# ModulePlayAndCharge.net
KiCad netlist of a schematic drawn in EasyEDA Pro
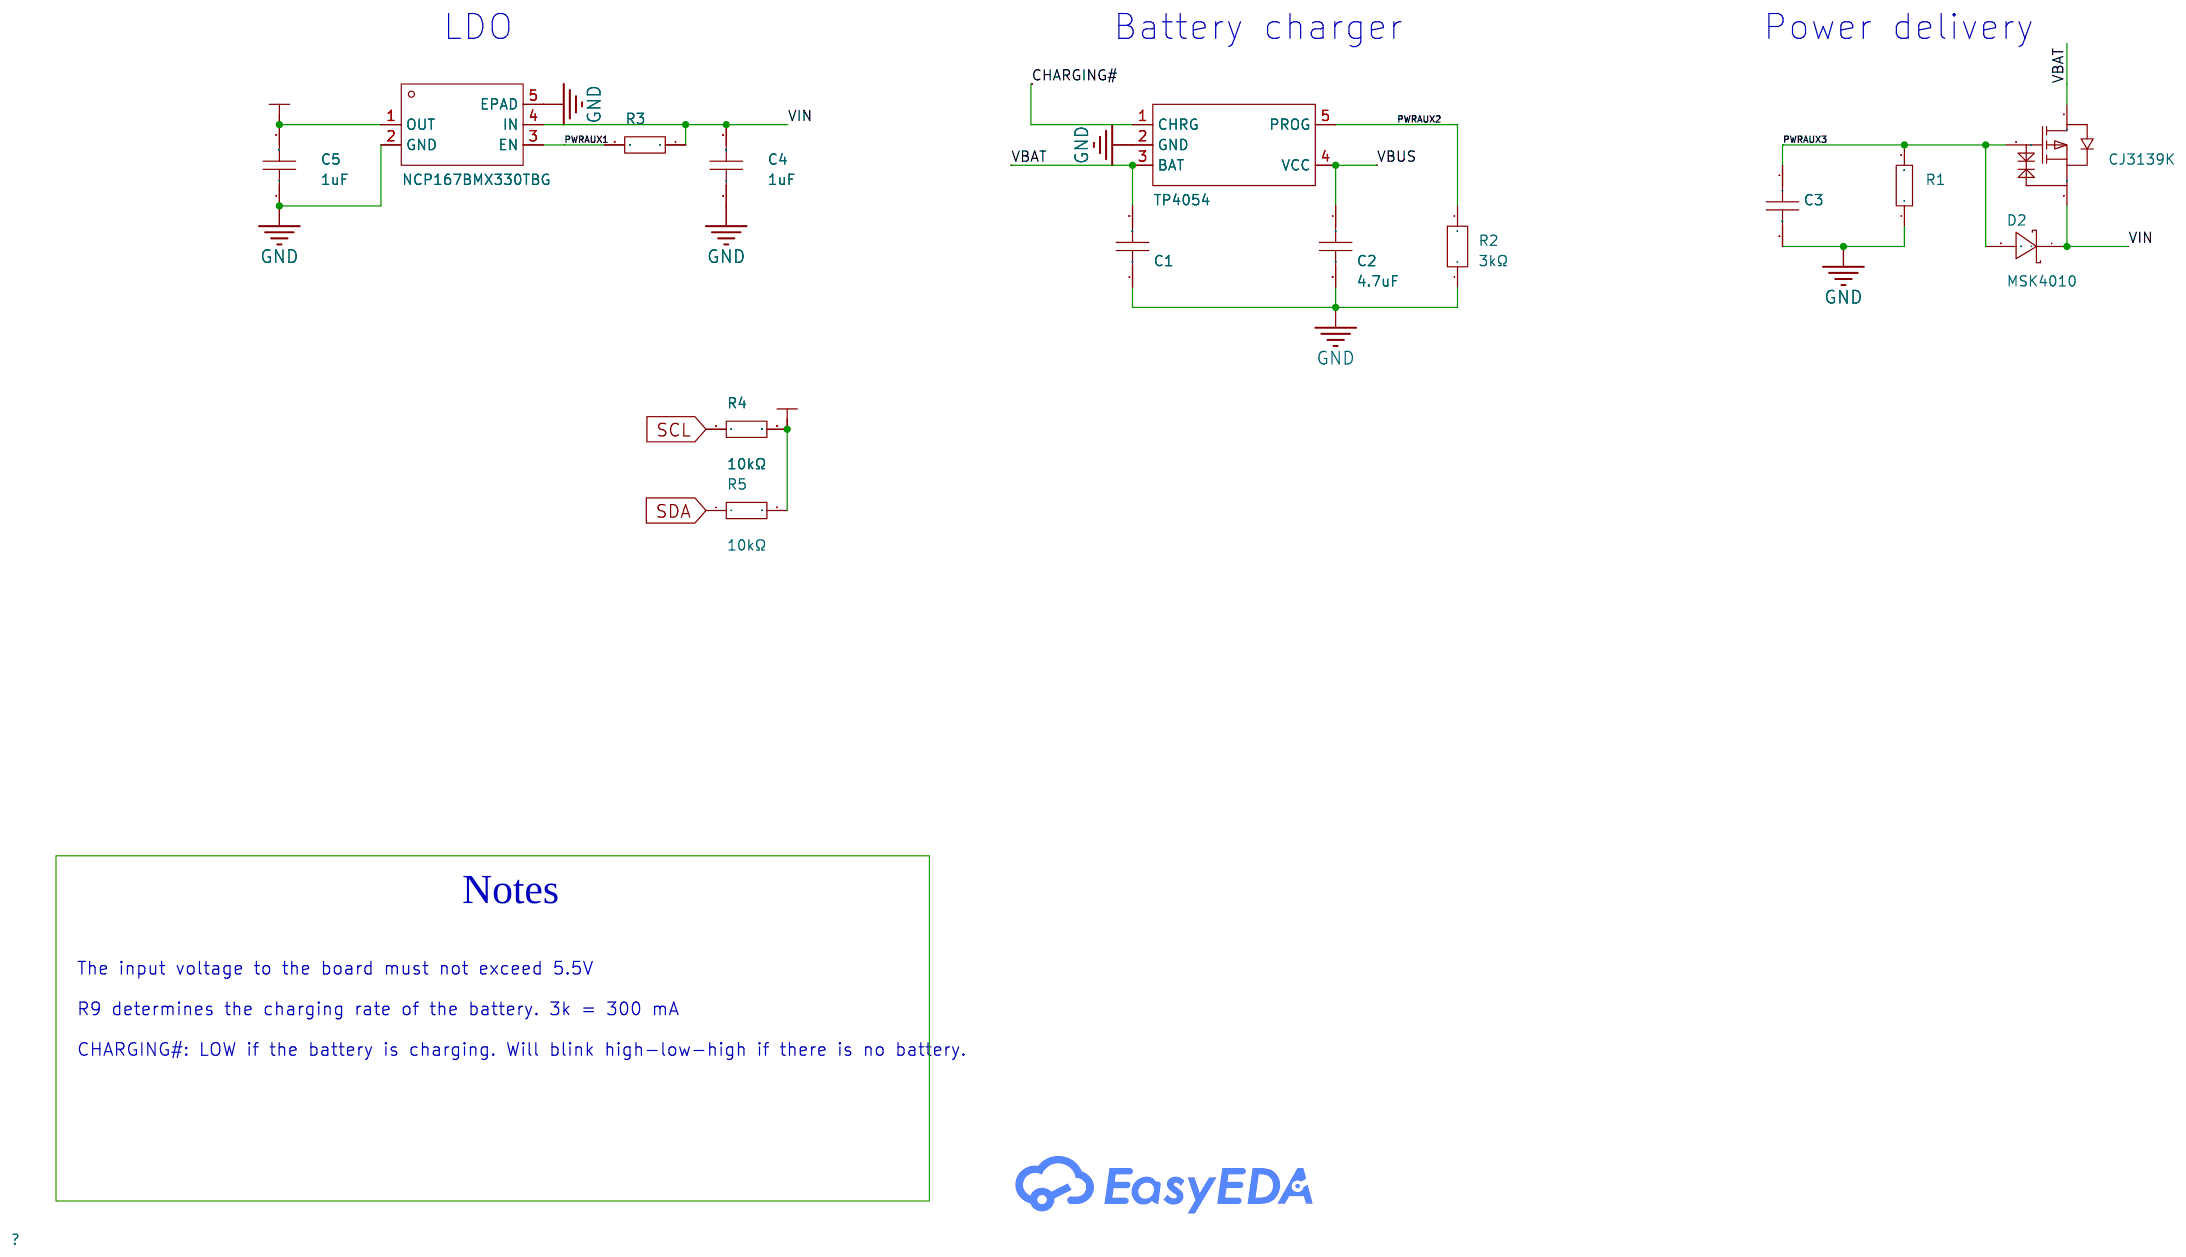
[diagram p0: Power]
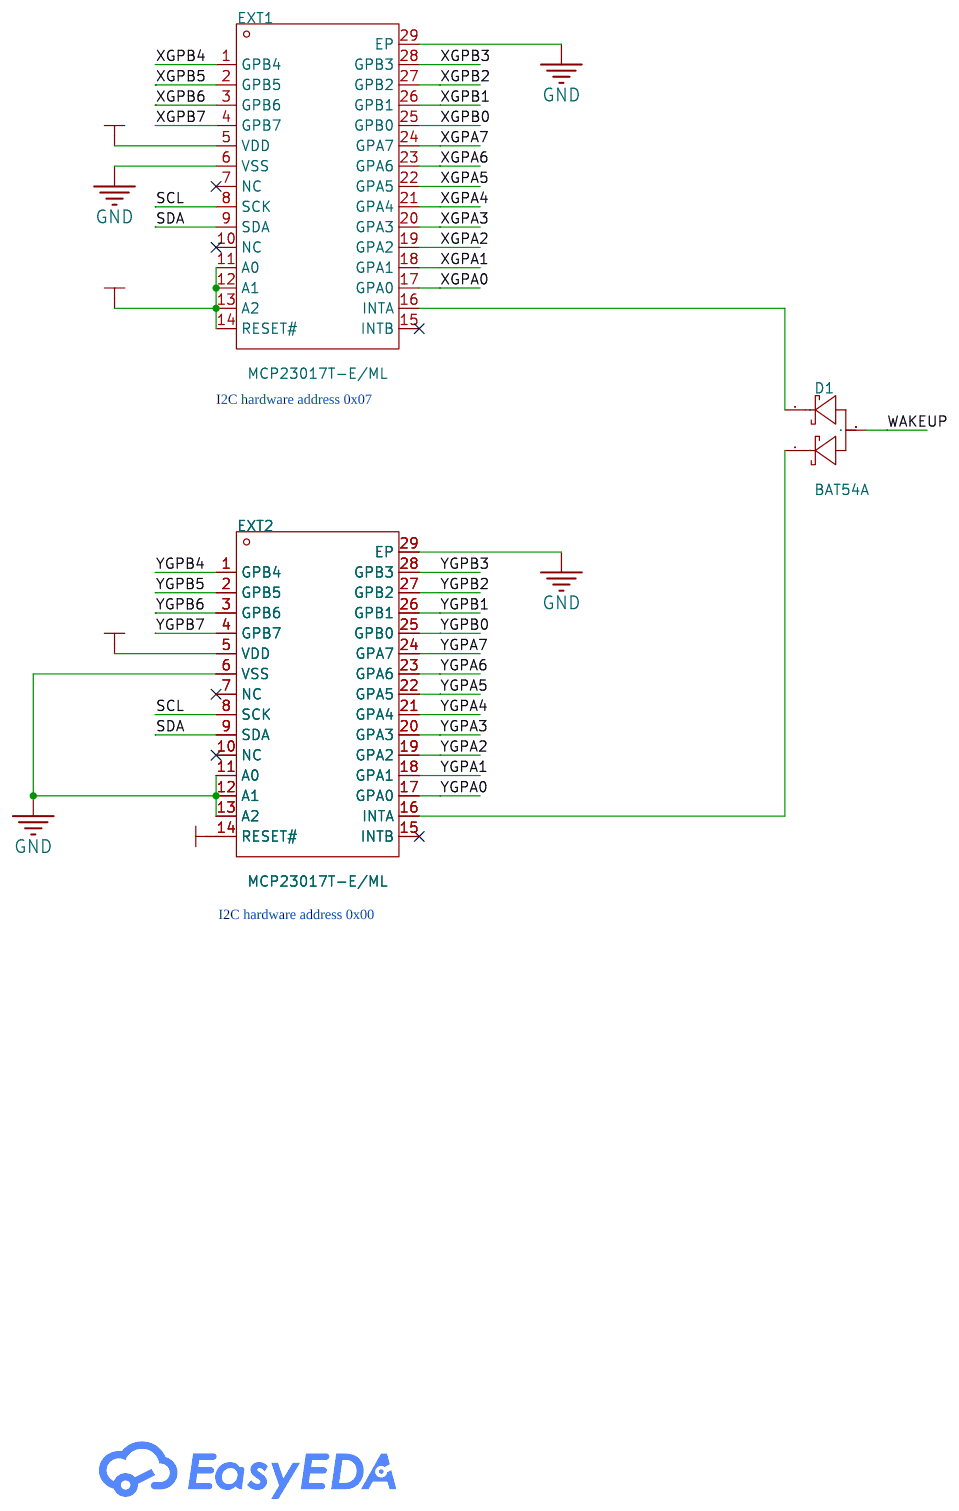
[diagram p1: GPIOExpanders]
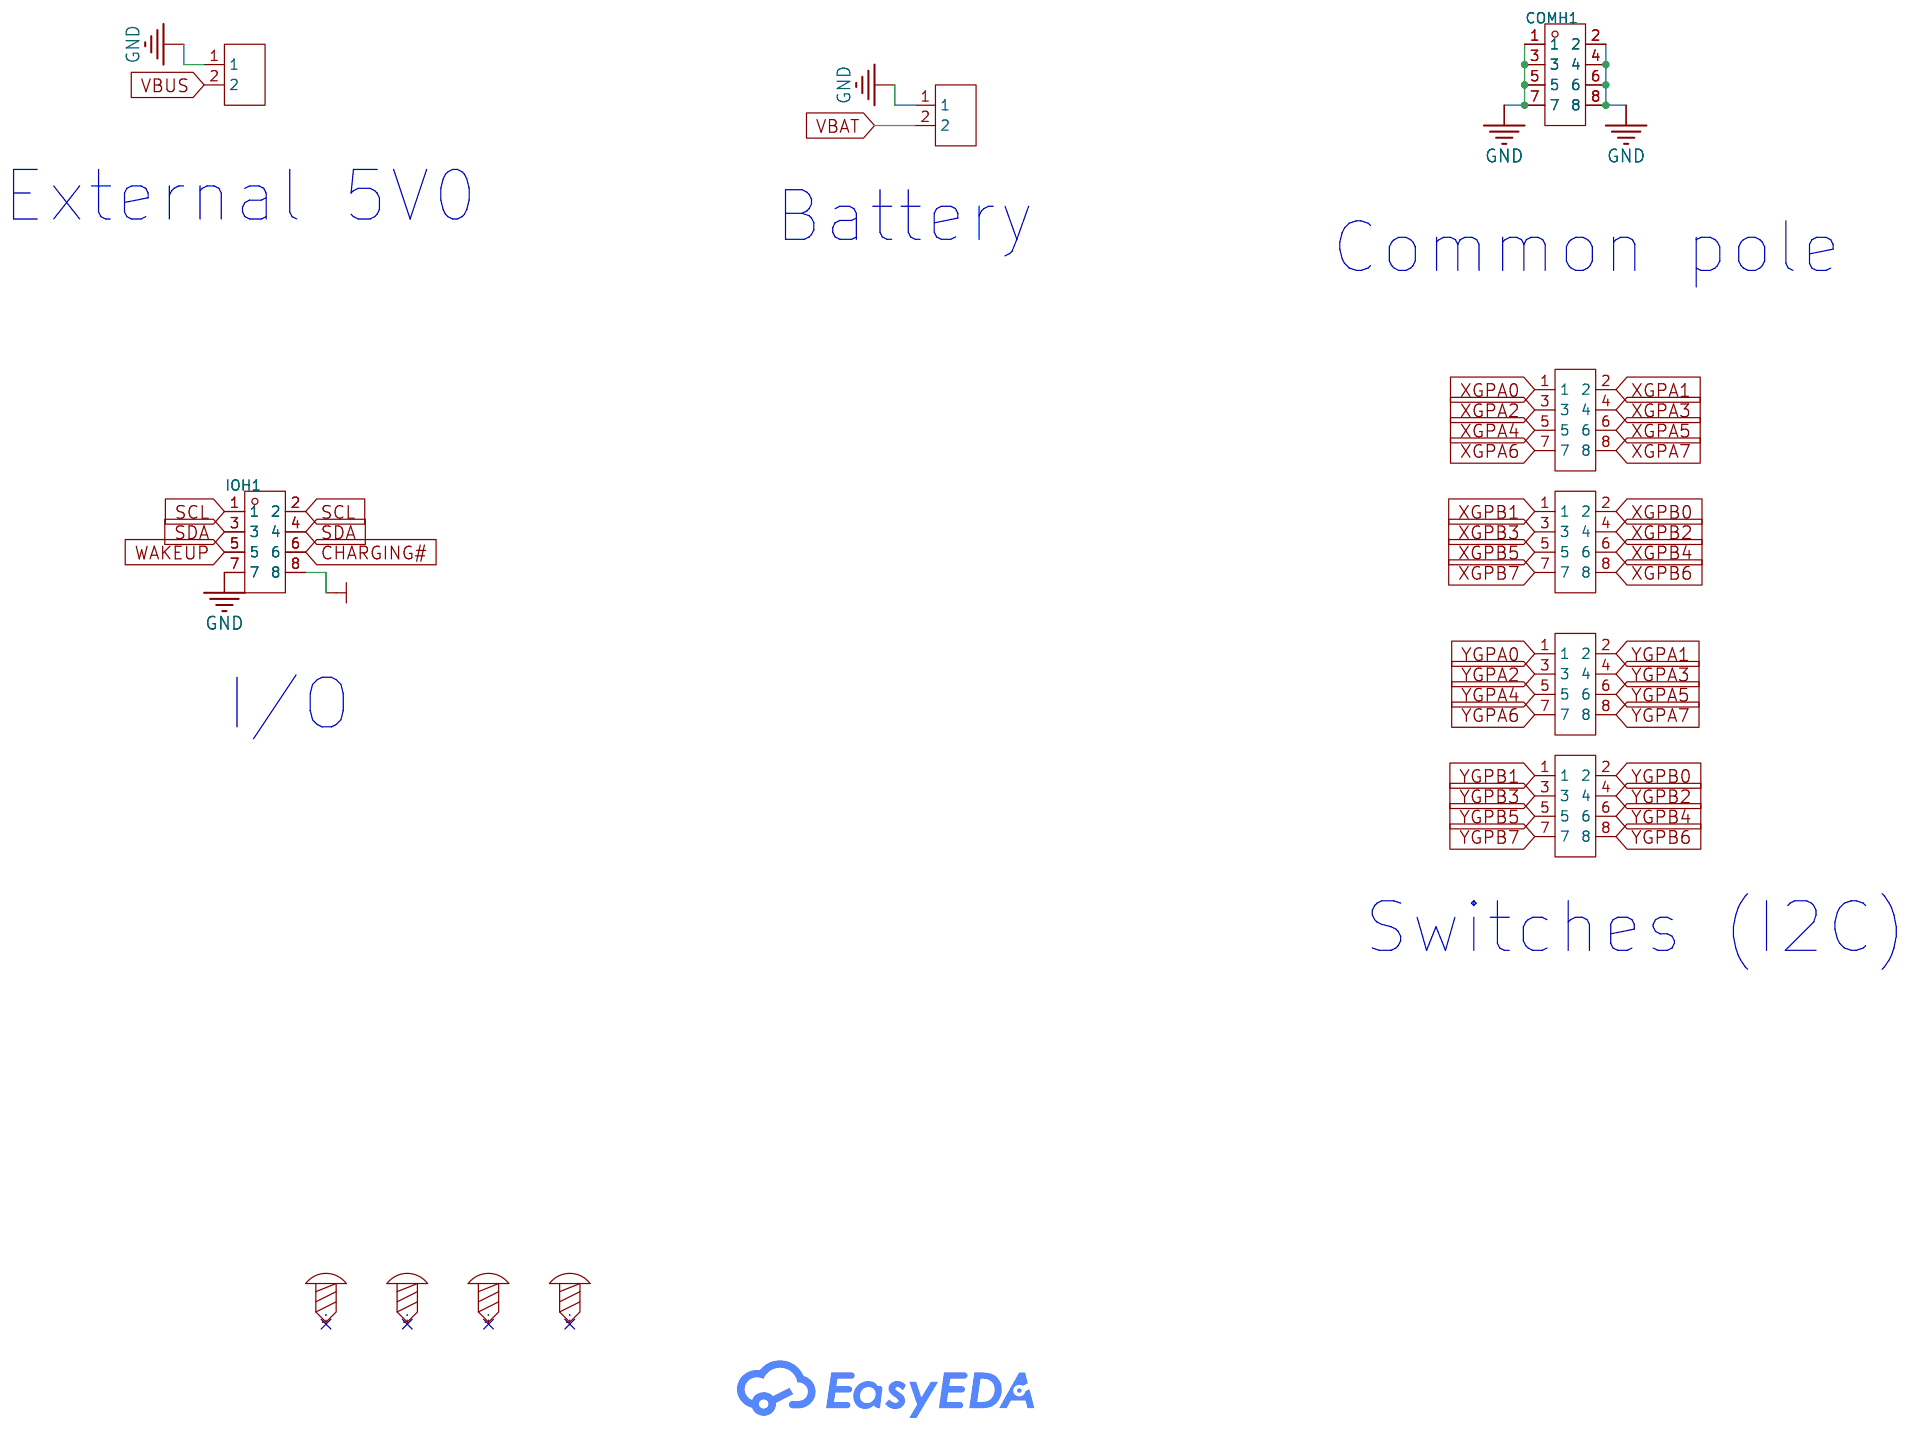
[diagram p2: Connectors]
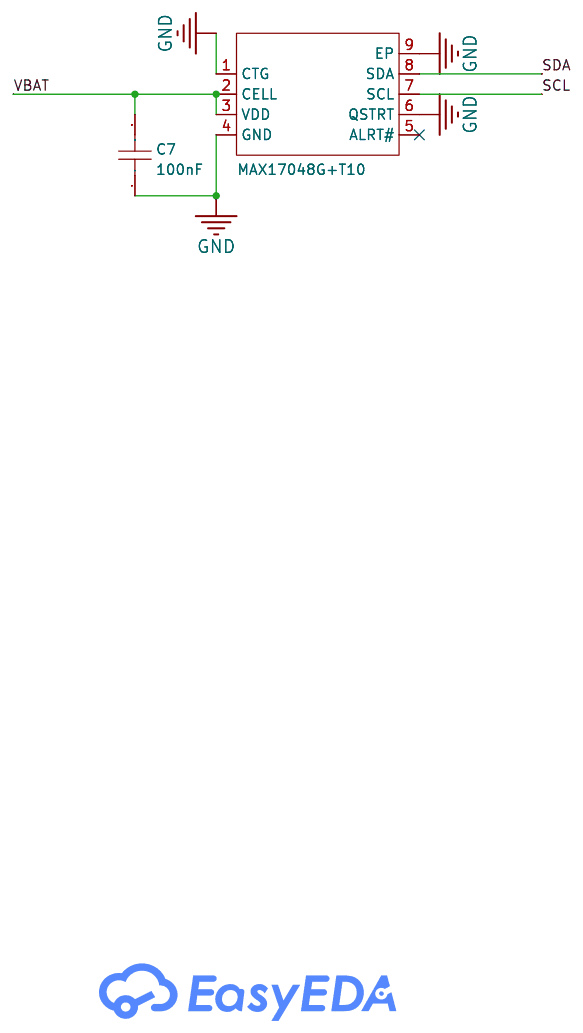
[diagram p3: FuelGauge]

(export (version "E")
  (design (tool "Eeschema 10.0.6"))
  (components
    (comp (ref "C1")
      (value "10uF")
      (footprint "easyedapro:C0603")
      (fields
        (field (name "Manufacturer Part") "CL10A106MQ8NNNC")
        (field (name "Manufacturer") "SAMSUNG(三星)")
      )
      (libsource (lib "easyedapro") (part "CL10A106MQ8NNNC"))
    )
    (comp (ref "C2")
      (value "4.7uF")
      (fields
        (field (name "Manufacturer Part") "CL05A475MP5NRNC")
        (field (name "Manufacturer") "SAMSUNG(三星)")
      )
      (libsource (lib "easyedapro") (part "CAP"))
    )
    (comp (ref "C3")
      (value "10uF")
      (footprint "easyedapro:C0603")
      (fields
        (field (name "Manufacturer Part") "CL10A106MQ8NNNC")
        (field (name "Manufacturer") "SAMSUNG(三星)")
      )
      (libsource (lib "easyedapro") (part "CL10A106MQ8NNNC"))
    )
    (comp (ref "C4")
      (value "1uF")
      (footprint "easyedapro:C0603")
      (fields
        (field (name "Manufacturer Part") "CL10A105KB8NNNC")
        (field (name "Manufacturer") "SAMSUNG(三星)")
      )
      (libsource (lib "easyedapro") (part "CL10A105KB8NNNC"))
    )
    (comp (ref "C5")
      (value "1uF")
      (footprint "easyedapro:C0603")
      (fields
        (field (name "Manufacturer Part") "CL10A105KB8NNNC")
        (field (name "Manufacturer") "SAMSUNG(三星)")
      )
      (libsource (lib "easyedapro") (part "CL10A105KB8NNNC"))
    )
    (comp (ref "D2")
      (value "MSK4010")
      (footprint "easyedapro:SOD-523_L1.2-W0.8-LS1.6-RD")
      (fields (field (name "Manufacturer") "SHIKUES(时科)"))
      (libsource (lib "easyedapro") (part "MSK4010"))
    )
    (comp (ref "Q1")
      (value "CJ3139K")
      (footprint "easyedapro:SOT-723_L1.2-W0.8-P0.40-LS1.2-BR")
      (fields (field (name "Manufacturer") "CJ(江苏长电/长晶)"))
      (libsource (lib "easyedapro") (part "CJ3139K"))
    )
    (comp (ref "R1")
      (value "100kΩ")
      (footprint "easyedapro:R0402")
      (fields
        (field (name "Manufacturer Part") "0402WGF1003TCE")
        (field (name "Manufacturer") "UNI-ROYAL(厚声)")
      )
      (libsource (lib "easyedapro") (part "0402WGF1003TCE"))
    )
    (comp (ref "R2")
      (value "3kΩ")
      (footprint "easyedapro:R0402")
      (fields (field (name "Manufacturer Part") "FRC0402F3001TS") (field (name "Manufacturer") "FOJAN(富捷)"))
      (libsource (lib "easyedapro") (part "FRC0402F3001TS"))
    )
    (comp (ref "R3")
      (value "100kΩ")
      (footprint "easyedapro:R0402")
      (fields
        (field (name "Manufacturer Part") "0402WGF1003TCE")
        (field (name "Manufacturer") "UNI-ROYAL(厚声)")
      )
      (libsource (lib "easyedapro") (part "0402WGF1003TCE"))
    )
    (comp (ref "R4")
      (value "10kΩ")
      (footprint "easyedapro:R0402")
      (fields
        (field (name "Manufacturer Part") "0402WGF1002TCE")
        (field (name "Manufacturer") "UNI-ROYAL(厚声)")
      )
      (libsource (lib "easyedapro") (part "0402WGF1002TCE"))
    )
    (comp (ref "R5")
      (value "10kΩ")
      (footprint "easyedapro:R0402")
      (fields
        (field (name "Manufacturer Part") "0402WGF1002TCE")
        (field (name "Manufacturer") "UNI-ROYAL(厚声)")
      )
      (libsource (lib "easyedapro") (part "0402WGF1002TCE"))
    )
    (comp (ref "U2")
      (value "TP4054")
      (footprint "easyedapro:SOT-23-5_L2.9-W1.6-P0.95-LS2.8-BR")
      (fields (field (name "Manufacturer") "JSMSEMI(杰盛微)"))
      (libsource (lib "easyedapro") (part "TP4054_C5381776"))
    )
    (comp (ref "U3")
      (value "NCP167BMX330TBG")
      (footprint "easyedapro:XDFN-4_L1.0-W1.0-P0.65-BL-EP")
      (fields (field (name "Manufacturer") "onsemi(安森美)"))
      (libsource (lib "easyedapro") (part "NCP167BMX330TBG"))
    )
    (comp (ref "D1")
      (value "BAT54A")
      (footprint "easyedapro:SOT-23-3_L2.9-W1.3-P1.90-LS2.4-BR")
      (fields (field (name "Manufacturer") "TWGMC(台湾迪嘉)"))
      (libsource (lib "easyedapro") (part "BAT54A_C727124"))
    )
    (comp (ref "EXT1")
      (value "MCP23017T-E/ML")
      (footprint "easyedapro:QFN-28_L6.0-W6.0-P0.65-BL-EP3.7")
      (fields (field (name "Manufacturer") "MICROCHIP(美国微芯)"))
      (libsource (lib "easyedapro") (part "MCP23017T-E/ML"))
    )
    (comp (ref "EXT2")
      (value "MCP23017T-E/ML")
      (footprint "easyedapro:QFN-28_L6.0-W6.0-P0.65-BL-EP3.7")
      (fields (field (name "Manufacturer") "MICROCHIP(美国微芯)"))
      (libsource (lib "easyedapro") (part "MCP23017T-E/ML"))
    )
    (comp (ref "BATTH1")
      (value "PZ254R-11-02P")
      (footprint "easyedapro:HDR-TH_2P-P2.54-H-M-W10.4")
      (fields (field (name "Manufacturer") "XFCN(兴飞)"))
      (libsource (lib "easyedapro") (part "PZ254R-11-02P"))
    )
    (comp (ref "COMH1")
      (value "PZ254R-12-8P")
      (fields (field (name "Manufacturer") "XFCN(兴飞)"))
      (libsource (lib "easyedapro") (part "PH2.54-07-04PWS"))
    )
    (comp (ref "IOH1")
      (value "PZ254R-12-8P")
      (fields (field (name "Manufacturer") "XFCN(兴飞)"))
      (libsource (lib "easyedapro") (part "PH2.54-07-04PWS"))
    )
    (comp (ref "PWRH1")
      (value "PZ254R-11-02P")
      (footprint "easyedapro:HDR-TH_2P-P2.54-H-M-W10.4")
      (fields (field (name "Manufacturer") "XFCN(兴飞)"))
      (libsource (lib "easyedapro") (part "PZ254R-11-02P"))
    )
    (comp (ref "SCREW1")
      (value "~")
      (footprint "easyedapro:Screw-Hole-M2")
      (libsource (lib "easyedapro") (part "Screw-Hole"))
    )
    (comp (ref "SCREW2")
      (value "~")
      (footprint "easyedapro:Screw-Hole-M2")
      (libsource (lib "easyedapro") (part "Screw-Hole"))
    )
    (comp (ref "SCREW3")
      (value "~")
      (footprint "easyedapro:Screw-Hole-M2")
      (libsource (lib "easyedapro") (part "Screw-Hole"))
    )
    (comp (ref "SCREW4")
      (value "~")
      (footprint "easyedapro:Screw-Hole-M2")
      (libsource (lib "easyedapro") (part "Screw-Hole"))
    )
    (comp (ref "XH1")
      (value "PZ254R-12-8P")
      (footprint "easyedapro:HDR-TH_8P-P2.54-H-M-R2-C4-S2.54")
      (fields (field (name "Manufacturer") "XFCN(兴飞)"))
      (libsource (lib "easyedapro") (part "PZ254R-12-8P"))
    )
    (comp (ref "XH2")
      (value "PZ254R-12-8P")
      (footprint "easyedapro:HDR-TH_8P-P2.54-H-M-R2-C4-S2.54")
      (fields (field (name "Manufacturer") "XFCN(兴飞)"))
      (libsource (lib "easyedapro") (part "PZ254R-12-8P"))
    )
    (comp (ref "YH1")
      (value "PZ254R-12-8P")
      (footprint "easyedapro:HDR-TH_8P-P2.54-H-M-R2-C4-S2.54")
      (fields (field (name "Manufacturer") "XFCN(兴飞)"))
      (libsource (lib "easyedapro") (part "PZ254R-12-8P"))
    )
    (comp (ref "YH2")
      (value "PZ254R-12-8P")
      (footprint "easyedapro:HDR-TH_8P-P2.54-H-M-R2-C4-S2.54")
      (fields (field (name "Manufacturer") "XFCN(兴飞)"))
      (libsource (lib "easyedapro") (part "PZ254R-12-8P"))
    )
    (comp (ref "C7")
      (value "100nF")
      (footprint "easyedapro:C0603")
      (description "Capacitance:100nF Tolerance:±10% Tolerance:±10% Voltage Rating:50V Temperature Coefficient:X7R")
      (fields
        (field (name "Manufacturer Part") "CC0603KRX7R9BB104")
        (field (name "Manufacturer") "YAGEO(国巨)")
      )
      (libsource (lib "easyedapro") (part "CC0603KRX7R9BB104"))
    )
    (comp (ref "U4")
      (value "MAX17048G+T10")
      (footprint "easyedapro:TDFN-8_L2.0-W2.0-P0.50-BL-EP1.2")
      (fields (field (name "Manufacturer") "ADI(亚德诺)/MAXIM(美信)"))
      (libsource (lib "easyedapro") (part "MAX17048G+T10"))
    )
  )
  (nets
    (net (code "1") (name "3V3") (class "Default")
      (node (ref "C5") (pin "2") (pinfunction "2_2") (pintype "unspecified"))
      (node (ref "EXT1") (pin "11") (pinfunction "A0_11") (pintype "unspecified"))
      (node (ref "EXT1") (pin "12") (pinfunction "A1_12") (pintype "unspecified"))
      (node (ref "EXT1") (pin "13") (pinfunction "A2_13") (pintype "unspecified"))
      (node (ref "EXT1") (pin "14") (pinfunction "RESET#_14") (pintype "unspecified"))
      (node (ref "EXT1") (pin "5") (pinfunction "VDD_5") (pintype "unspecified"))
      (node (ref "EXT2") (pin "14") (pinfunction "RESET#_14") (pintype "unspecified"))
      (node (ref "EXT2") (pin "5") (pinfunction "VDD_5") (pintype "unspecified"))
      (node (ref "IOH1") (pin "8") (pinfunction "8_8") (pintype "unspecified"))
      (node (ref "R4") (pin "2") (pinfunction "2_2") (pintype "input"))
      (node (ref "R5") (pin "2") (pinfunction "2_2") (pintype "input"))
      (node (ref "U3") (pin "1") (pinfunction "OUT_1") (pintype "unspecified"))
    )
    (net (code "2") (name "CHARGING#") (class "Default")
      (node (ref "IOH1") (pin "6") (pinfunction "6_6") (pintype "unspecified"))
      (node (ref "U2") (pin "1") (pinfunction "CHRG_1") (pintype "unspecified"))
    )
    (net (code "3") (name "GND") (class "Default")
      (node (ref "BATTH1") (pin "1") (pinfunction "1_1") (pintype "unspecified"))
      (node (ref "C1") (pin "1") (pinfunction "1_1") (pintype "input"))
      (node (ref "C2") (pin "2") (pinfunction "2_2") (pintype "input"))
      (node (ref "C3") (pin "2") (pinfunction "2_2") (pintype "input"))
      (node (ref "C4") (pin "1") (pinfunction "1_1") (pintype "unspecified"))
      (node (ref "C5") (pin "1") (pinfunction "1_1") (pintype "unspecified"))
      (node (ref "C7") (pin "1") (pinfunction "1_1") (pintype "unspecified"))
      (node (ref "COMH1") (pin "1") (pinfunction "1_1") (pintype "unspecified"))
      (node (ref "COMH1") (pin "2") (pinfunction "2_2") (pintype "unspecified"))
      (node (ref "COMH1") (pin "3") (pinfunction "3_3") (pintype "unspecified"))
      (node (ref "COMH1") (pin "4") (pinfunction "4_4") (pintype "unspecified"))
      (node (ref "COMH1") (pin "5") (pinfunction "5_5") (pintype "unspecified"))
      (node (ref "COMH1") (pin "6") (pinfunction "6_6") (pintype "unspecified"))
      (node (ref "COMH1") (pin "7") (pinfunction "7_7") (pintype "unspecified"))
      (node (ref "COMH1") (pin "8") (pinfunction "8_8") (pintype "unspecified"))
      (node (ref "EXT1") (pin "29") (pinfunction "EP_29") (pintype "unspecified"))
      (node (ref "EXT1") (pin "6") (pinfunction "VSS_6") (pintype "unspecified"))
      (node (ref "EXT2") (pin "11") (pinfunction "A0_11") (pintype "unspecified"))
      (node (ref "EXT2") (pin "12") (pinfunction "A1_12") (pintype "unspecified"))
      (node (ref "EXT2") (pin "13") (pinfunction "A2_13") (pintype "unspecified"))
      (node (ref "EXT2") (pin "29") (pinfunction "EP_29") (pintype "unspecified"))
      (node (ref "EXT2") (pin "6") (pinfunction "VSS_6") (pintype "unspecified"))
      (node (ref "IOH1") (pin "7") (pinfunction "7_7") (pintype "unspecified"))
      (node (ref "PWRH1") (pin "1") (pinfunction "1_1") (pintype "unspecified"))
      (node (ref "R1") (pin "1") (pinfunction "1_1") (pintype "input"))
      (node (ref "R2") (pin "1") (pinfunction "1_1") (pintype "unspecified"))
      (node (ref "U2") (pin "2") (pinfunction "GND_2") (pintype "unspecified"))
      (node (ref "U3") (pin "2") (pinfunction "GND_2") (pintype "unspecified"))
      (node (ref "U3") (pin "5") (pinfunction "EPAD_5") (pintype "unspecified"))
      (node (ref "U4") (pin "1") (pinfunction "CTG_1") (pintype "unspecified"))
      (node (ref "U4") (pin "4") (pinfunction "GND_4") (pintype "unspecified"))
      (node (ref "U4") (pin "6") (pinfunction "QSTRT_6") (pintype "unspecified"))
      (node (ref "U4") (pin "9") (pinfunction "EP_9") (pintype "unspecified"))
    )
    (net (code "4") (name "Net-(EXT1-INTA)") (class "Default")
      (node (ref "D1") (pin "1") (pinfunction "A_1") (pintype "unspecified"))
      (node (ref "EXT1") (pin "16") (pinfunction "INTA_16") (pintype "unspecified"))
    )
    (net (code "5") (name "Net-(EXT2-INTA)") (class "Default")
      (node (ref "D1") (pin "2") (pinfunction "A_2") (pintype "unspecified"))
      (node (ref "EXT2") (pin "16") (pinfunction "INTA_16") (pintype "unspecified"))
    )
    (net (code "6") (name "PWRAUX1") (class "Default")
      (node (ref "R3") (pin "2") (pinfunction "2_2") (pintype "input"))
      (node (ref "U3") (pin "3") (pinfunction "EN_3") (pintype "unspecified"))
    )
    (net (code "7") (name "PWRAUX2") (class "Default")
      (node (ref "R2") (pin "2") (pinfunction "2_2") (pintype "unspecified"))
      (node (ref "U2") (pin "5") (pinfunction "PROG_5") (pintype "unspecified"))
    )
    (net (code "8") (name "PWRAUX3") (class "Default")
      (node (ref "C3") (pin "1") (pinfunction "1_1") (pintype "input"))
      (node (ref "D2") (pin "2") (pinfunction "2_2") (pintype "unspecified"))
      (node (ref "Q1") (pin "1") (pinfunction "G_1") (pintype "unspecified"))
      (node (ref "R1") (pin "2") (pinfunction "2_2") (pintype "input"))
    )
    (net (code "9") (name "SCL") (class "Default")
      (node (ref "EXT1") (pin "8") (pinfunction "SCK_8") (pintype "unspecified"))
      (node (ref "EXT2") (pin "8") (pinfunction "SCK_8") (pintype "unspecified"))
      (node (ref "IOH1") (pin "1") (pinfunction "1_1") (pintype "unspecified"))
      (node (ref "IOH1") (pin "2") (pinfunction "2_2") (pintype "unspecified"))
      (node (ref "R4") (pin "1") (pinfunction "1_1") (pintype "input"))
      (node (ref "U4") (pin "7") (pinfunction "SCL_7") (pintype "unspecified"))
    )
    (net (code "10") (name "SDA") (class "Default")
      (node (ref "EXT1") (pin "9") (pinfunction "SDA_9") (pintype "unspecified"))
      (node (ref "EXT2") (pin "9") (pinfunction "SDA_9") (pintype "unspecified"))
      (node (ref "IOH1") (pin "3") (pinfunction "3_3") (pintype "unspecified"))
      (node (ref "IOH1") (pin "4") (pinfunction "4_4") (pintype "unspecified"))
      (node (ref "R5") (pin "1") (pinfunction "1_1") (pintype "input"))
      (node (ref "U4") (pin "8") (pinfunction "SDA_8") (pintype "unspecified"))
    )
    (net (code "11") (name "VBAT") (class "Default")
      (node (ref "BATTH1") (pin "2") (pinfunction "2_2") (pintype "unspecified"))
      (node (ref "C1") (pin "2") (pinfunction "2_2") (pintype "input"))
      (node (ref "C7") (pin "2") (pinfunction "2_2") (pintype "unspecified"))
      (node (ref "Q1") (pin "3") (pinfunction "D_3") (pintype "unspecified"))
      (node (ref "U2") (pin "3") (pinfunction "BAT_3") (pintype "unspecified"))
      (node (ref "U4") (pin "2") (pinfunction "CELL_2") (pintype "unspecified"))
      (node (ref "U4") (pin "3") (pinfunction "VDD_3") (pintype "unspecified"))
    )
    (net (code "12") (name "VBUS") (class "Default")
      (node (ref "C2") (pin "1") (pinfunction "1_1") (pintype "input"))
      (node (ref "PWRH1") (pin "2") (pinfunction "2_2") (pintype "unspecified"))
      (node (ref "U2") (pin "4") (pinfunction "VCC_4") (pintype "unspecified"))
    )
    (net (code "13") (name "VIN") (class "Default")
      (node (ref "C4") (pin "2") (pinfunction "2_2") (pintype "unspecified"))
      (node (ref "D2") (pin "1") (pinfunction "1_1") (pintype "unspecified"))
      (node (ref "Q1") (pin "2") (pinfunction "S_2") (pintype "unspecified"))
      (node (ref "R3") (pin "1") (pinfunction "1_1") (pintype "input"))
      (node (ref "U3") (pin "4") (pinfunction "IN_4") (pintype "unspecified"))
    )
    (net (code "14") (name "WAKEUP") (class "Default")
      (node (ref "D1") (pin "3") (pinfunction "K_3") (pintype "unspecified"))
      (node (ref "IOH1") (pin "5") (pinfunction "5_5") (pintype "unspecified"))
    )
    (net (code "15") (name "XGPA0") (class "Default")
      (node (ref "EXT1") (pin "17") (pinfunction "GPA0_17") (pintype "unspecified"))
      (node (ref "XH1") (pin "1") (pinfunction "1_1") (pintype "unspecified"))
    )
    (net (code "16") (name "XGPA1") (class "Default")
      (node (ref "EXT1") (pin "18") (pinfunction "GPA1_18") (pintype "unspecified"))
      (node (ref "XH1") (pin "2") (pinfunction "2_2") (pintype "unspecified"))
    )
    (net (code "17") (name "XGPA2") (class "Default")
      (node (ref "EXT1") (pin "19") (pinfunction "GPA2_19") (pintype "unspecified"))
      (node (ref "XH1") (pin "3") (pinfunction "3_3") (pintype "unspecified"))
    )
    (net (code "18") (name "XGPA3") (class "Default")
      (node (ref "EXT1") (pin "20") (pinfunction "GPA3_20") (pintype "unspecified"))
      (node (ref "XH1") (pin "4") (pinfunction "4_4") (pintype "unspecified"))
    )
    (net (code "19") (name "XGPA4") (class "Default")
      (node (ref "EXT1") (pin "21") (pinfunction "GPA4_21") (pintype "unspecified"))
      (node (ref "XH1") (pin "5") (pinfunction "5_5") (pintype "unspecified"))
    )
    (net (code "20") (name "XGPA5") (class "Default")
      (node (ref "EXT1") (pin "22") (pinfunction "GPA5_22") (pintype "unspecified"))
      (node (ref "XH1") (pin "6") (pinfunction "6_6") (pintype "unspecified"))
    )
    (net (code "21") (name "XGPA6") (class "Default")
      (node (ref "EXT1") (pin "23") (pinfunction "GPA6_23") (pintype "unspecified"))
      (node (ref "XH1") (pin "7") (pinfunction "7_7") (pintype "unspecified"))
    )
    (net (code "22") (name "XGPA7") (class "Default")
      (node (ref "EXT1") (pin "24") (pinfunction "GPA7_24") (pintype "unspecified"))
      (node (ref "XH1") (pin "8") (pinfunction "8_8") (pintype "unspecified"))
    )
    (net (code "23") (name "XGPB0") (class "Default")
      (node (ref "EXT1") (pin "25") (pinfunction "GPB0_25") (pintype "unspecified"))
      (node (ref "XH2") (pin "2") (pinfunction "2_2") (pintype "unspecified"))
    )
    (net (code "24") (name "XGPB1") (class "Default")
      (node (ref "EXT1") (pin "26") (pinfunction "GPB1_26") (pintype "unspecified"))
      (node (ref "XH2") (pin "1") (pinfunction "1_1") (pintype "unspecified"))
    )
    (net (code "25") (name "XGPB2") (class "Default")
      (node (ref "EXT1") (pin "27") (pinfunction "GPB2_27") (pintype "unspecified"))
      (node (ref "XH2") (pin "4") (pinfunction "4_4") (pintype "unspecified"))
    )
    (net (code "26") (name "XGPB3") (class "Default")
      (node (ref "EXT1") (pin "28") (pinfunction "GPB3_28") (pintype "unspecified"))
      (node (ref "XH2") (pin "3") (pinfunction "3_3") (pintype "unspecified"))
    )
    (net (code "27") (name "XGPB4") (class "Default")
      (node (ref "EXT1") (pin "1") (pinfunction "GPB4_1") (pintype "unspecified"))
      (node (ref "XH2") (pin "6") (pinfunction "6_6") (pintype "unspecified"))
    )
    (net (code "28") (name "XGPB5") (class "Default")
      (node (ref "EXT1") (pin "2") (pinfunction "GPB5_2") (pintype "unspecified"))
      (node (ref "XH2") (pin "5") (pinfunction "5_5") (pintype "unspecified"))
    )
    (net (code "29") (name "XGPB6") (class "Default")
      (node (ref "EXT1") (pin "3") (pinfunction "GPB6_3") (pintype "unspecified"))
      (node (ref "XH2") (pin "8") (pinfunction "8_8") (pintype "unspecified"))
    )
    (net (code "30") (name "XGPB7") (class "Default")
      (node (ref "EXT1") (pin "4") (pinfunction "GPB7_4") (pintype "unspecified"))
      (node (ref "XH2") (pin "7") (pinfunction "7_7") (pintype "unspecified"))
    )
    (net (code "31") (name "YGPA0") (class "Default")
      (node (ref "EXT2") (pin "17") (pinfunction "GPA0_17") (pintype "unspecified"))
      (node (ref "YH1") (pin "1") (pinfunction "1_1") (pintype "unspecified"))
    )
    (net (code "32") (name "YGPA1") (class "Default")
      (node (ref "EXT2") (pin "18") (pinfunction "GPA1_18") (pintype "unspecified"))
      (node (ref "YH1") (pin "2") (pinfunction "2_2") (pintype "unspecified"))
    )
    (net (code "33") (name "YGPA2") (class "Default")
      (node (ref "EXT2") (pin "19") (pinfunction "GPA2_19") (pintype "unspecified"))
      (node (ref "YH1") (pin "3") (pinfunction "3_3") (pintype "unspecified"))
    )
    (net (code "34") (name "YGPA3") (class "Default")
      (node (ref "EXT2") (pin "20") (pinfunction "GPA3_20") (pintype "unspecified"))
      (node (ref "YH1") (pin "4") (pinfunction "4_4") (pintype "unspecified"))
    )
    (net (code "35") (name "YGPA4") (class "Default")
      (node (ref "EXT2") (pin "21") (pinfunction "GPA4_21") (pintype "unspecified"))
      (node (ref "YH1") (pin "5") (pinfunction "5_5") (pintype "unspecified"))
    )
    (net (code "36") (name "YGPA5") (class "Default")
      (node (ref "EXT2") (pin "22") (pinfunction "GPA5_22") (pintype "unspecified"))
      (node (ref "YH1") (pin "6") (pinfunction "6_6") (pintype "unspecified"))
    )
    (net (code "37") (name "YGPA6") (class "Default")
      (node (ref "EXT2") (pin "23") (pinfunction "GPA6_23") (pintype "unspecified"))
      (node (ref "YH1") (pin "7") (pinfunction "7_7") (pintype "unspecified"))
    )
    (net (code "38") (name "YGPA7") (class "Default")
      (node (ref "EXT2") (pin "24") (pinfunction "GPA7_24") (pintype "unspecified"))
      (node (ref "YH1") (pin "8") (pinfunction "8_8") (pintype "unspecified"))
    )
    (net (code "39") (name "YGPB0") (class "Default")
      (node (ref "EXT2") (pin "25") (pinfunction "GPB0_25") (pintype "unspecified"))
      (node (ref "YH2") (pin "2") (pinfunction "2_2") (pintype "unspecified"))
    )
    (net (code "40") (name "YGPB1") (class "Default")
      (node (ref "EXT2") (pin "26") (pinfunction "GPB1_26") (pintype "unspecified"))
      (node (ref "YH2") (pin "1") (pinfunction "1_1") (pintype "unspecified"))
    )
    (net (code "41") (name "YGPB2") (class "Default")
      (node (ref "EXT2") (pin "27") (pinfunction "GPB2_27") (pintype "unspecified"))
      (node (ref "YH2") (pin "4") (pinfunction "4_4") (pintype "unspecified"))
    )
    (net (code "42") (name "YGPB3") (class "Default")
      (node (ref "EXT2") (pin "28") (pinfunction "GPB3_28") (pintype "unspecified"))
      (node (ref "YH2") (pin "3") (pinfunction "3_3") (pintype "unspecified"))
    )
    (net (code "43") (name "YGPB4") (class "Default")
      (node (ref "EXT2") (pin "1") (pinfunction "GPB4_1") (pintype "unspecified"))
      (node (ref "YH2") (pin "6") (pinfunction "6_6") (pintype "unspecified"))
    )
    (net (code "44") (name "YGPB5") (class "Default")
      (node (ref "EXT2") (pin "2") (pinfunction "GPB5_2") (pintype "unspecified"))
      (node (ref "YH2") (pin "5") (pinfunction "5_5") (pintype "unspecified"))
    )
    (net (code "45") (name "YGPB6") (class "Default")
      (node (ref "EXT2") (pin "3") (pinfunction "GPB6_3") (pintype "unspecified"))
      (node (ref "YH2") (pin "8") (pinfunction "8_8") (pintype "unspecified"))
    )
    (net (code "46") (name "YGPB7") (class "Default")
      (node (ref "EXT2") (pin "4") (pinfunction "GPB7_4") (pintype "unspecified"))
      (node (ref "YH2") (pin "7") (pinfunction "7_7") (pintype "unspecified"))
    )
    (net (code "47") (name "unconnected-(EXT1-INTB-Pad15)") (class "Default")
      (node (ref "EXT1") (pin "15") (pinfunction "INTB_15") (pintype "unspecified+no_connect"))
    )
    (net (code "48") (name "unconnected-(EXT1-NC-Pad7)") (class "Default")
      (node (ref "EXT1") (pin "7") (pinfunction "NC_7") (pintype "unspecified+no_connect"))
    )
    (net (code "49") (name "unconnected-(EXT1-NC-Pad10)") (class "Default")
      (node (ref "EXT1") (pin "10") (pinfunction "NC_10") (pintype "unspecified+no_connect"))
    )
    (net (code "50") (name "unconnected-(EXT2-INTB-Pad15)") (class "Default")
      (node (ref "EXT2") (pin "15") (pinfunction "INTB_15") (pintype "unspecified+no_connect"))
    )
    (net (code "51") (name "unconnected-(EXT2-NC-Pad7)") (class "Default")
      (node (ref "EXT2") (pin "7") (pinfunction "NC_7") (pintype "unspecified+no_connect"))
    )
    (net (code "52") (name "unconnected-(EXT2-NC-Pad10)") (class "Default")
      (node (ref "EXT2") (pin "10") (pinfunction "NC_10") (pintype "unspecified+no_connect"))
    )
    (net (code "53") (name "unconnected-(SCREW1-Pad1)") (class "Default")
      (node (ref "SCREW1") (pin "1") (pinfunction "1_1") (pintype "input+no_connect"))
    )
    (net (code "54") (name "unconnected-(SCREW2-Pad1)") (class "Default")
      (node (ref "SCREW2") (pin "1") (pinfunction "1_1") (pintype "input+no_connect"))
    )
    (net (code "55") (name "unconnected-(SCREW3-Pad1)") (class "Default")
      (node (ref "SCREW3") (pin "1") (pinfunction "1_1") (pintype "input+no_connect"))
    )
    (net (code "56") (name "unconnected-(SCREW4-Pad1)") (class "Default")
      (node (ref "SCREW4") (pin "1") (pinfunction "1_1") (pintype "input+no_connect"))
    )
    (net (code "57") (name "unconnected-(U4-ALRT#-Pad5)") (class "Default")
      (node (ref "U4") (pin "5") (pinfunction "ALRT#_5") (pintype "unspecified+no_connect"))
    )
  )
)
